# Schematic.net
KiCad netlist of a schematic drawn in Altium Designer
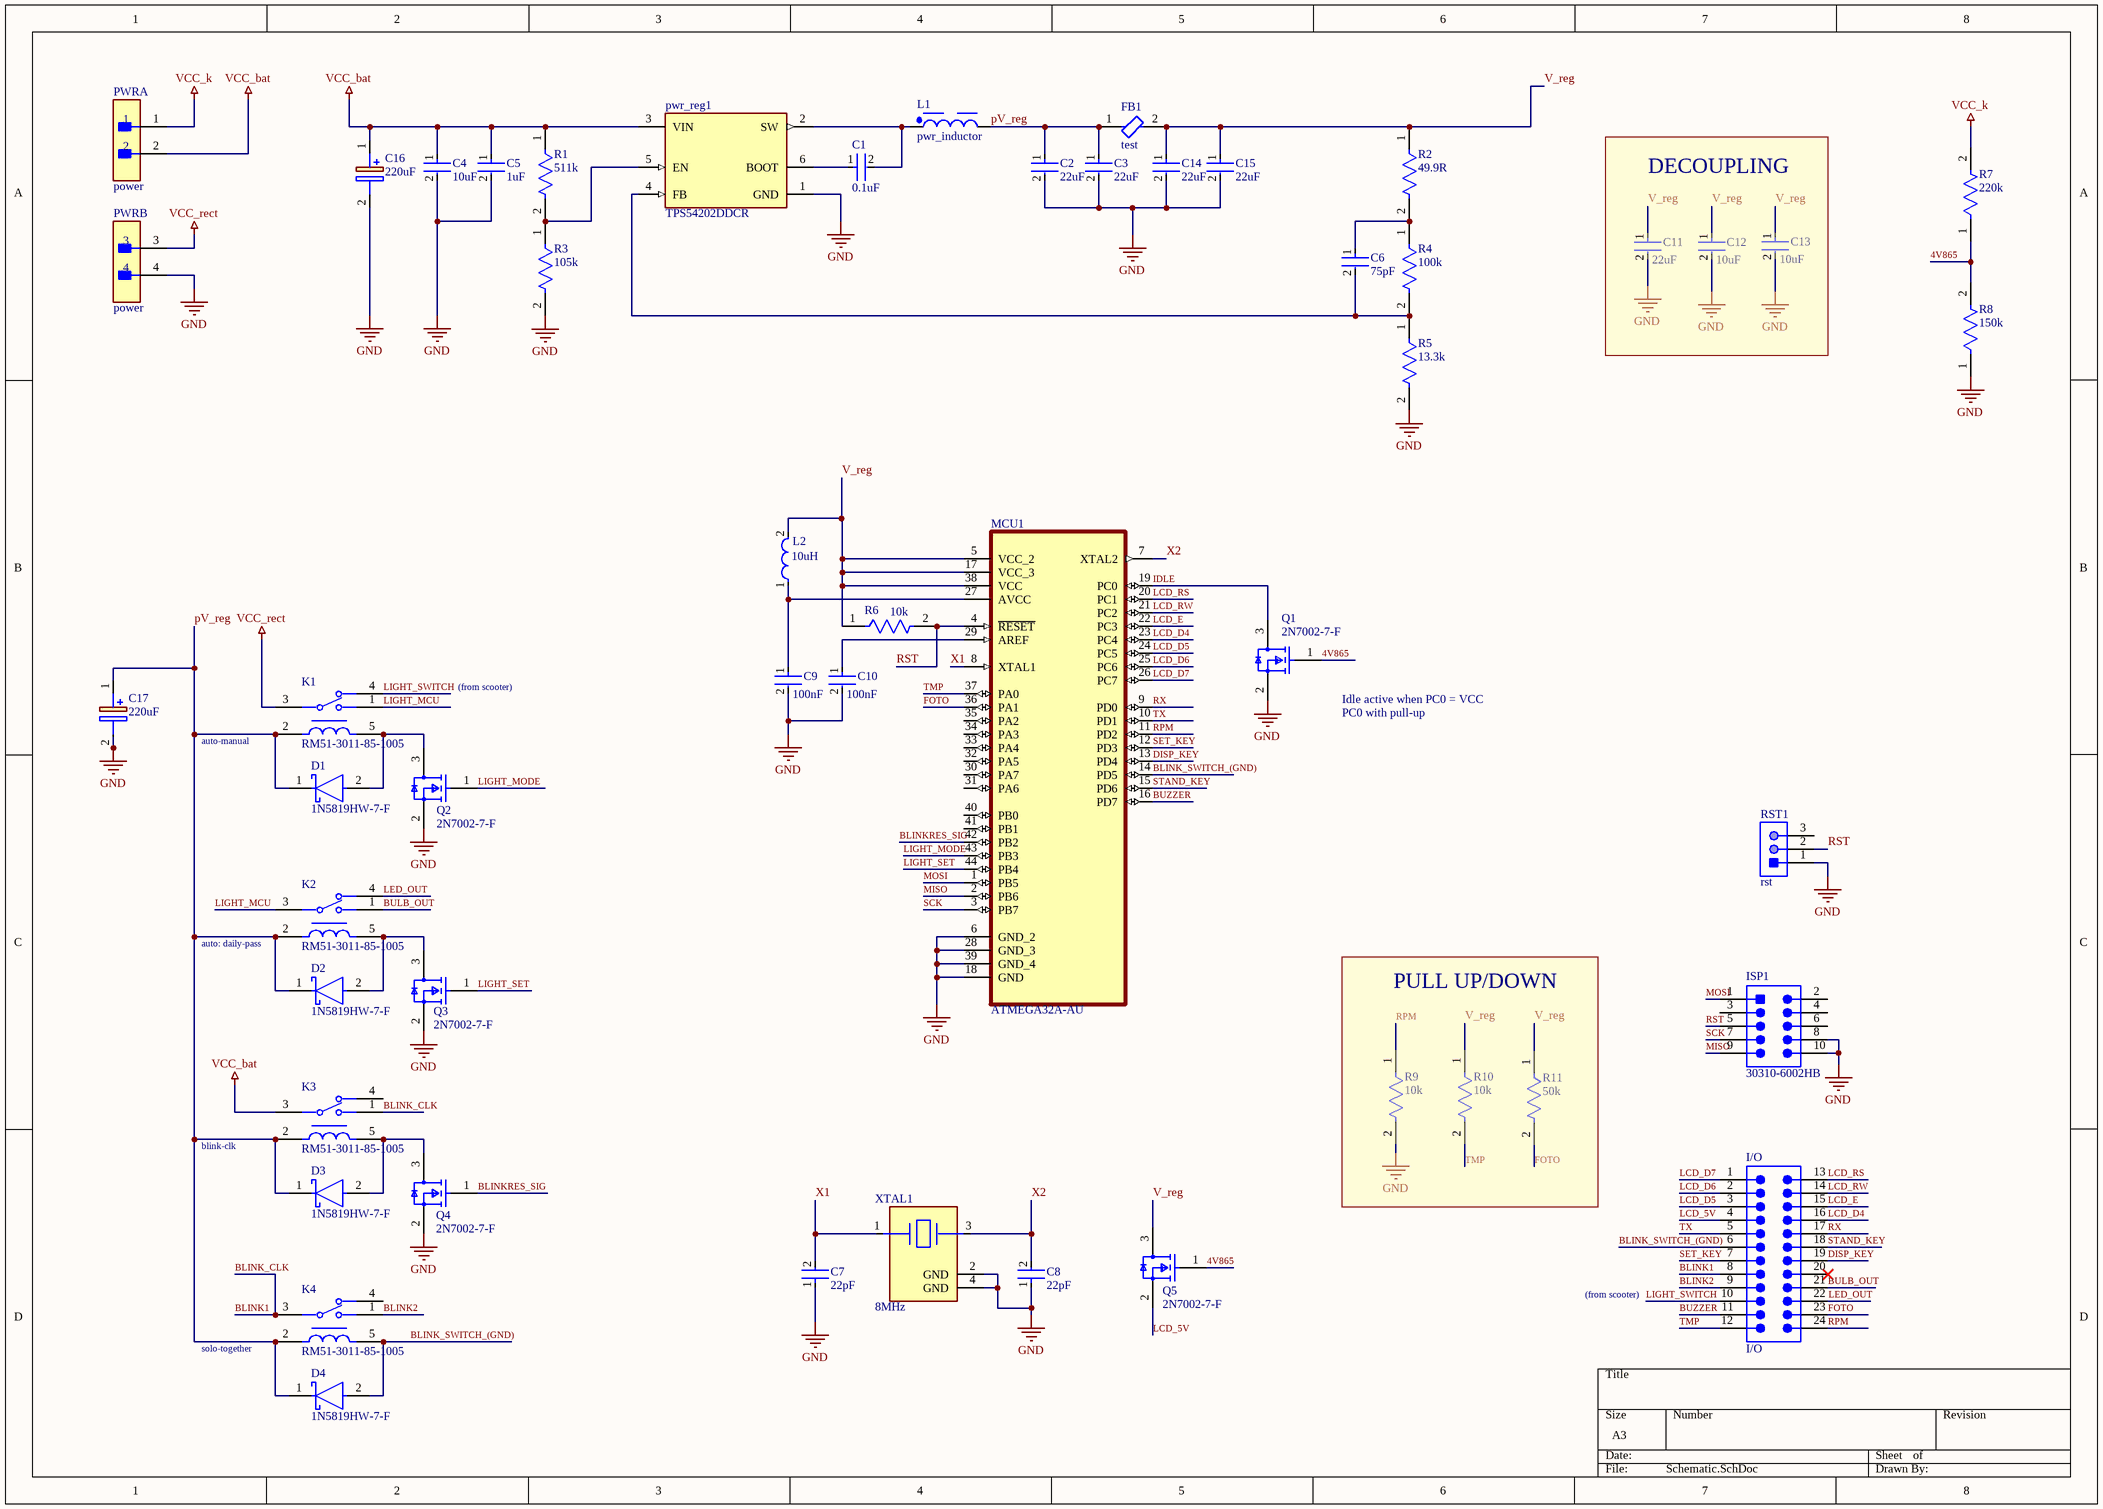
[diagram p0: Schematic.SchDoc]

(export (version "E")
  (design (tool "Eeschema 10.0.6"))
  (components
    (comp (ref "C1")
      (value "0.1uF")
      (footprint "FP-CL10-IPC_A")
      (description "Cap Ceramic 0.1uF 25V SMD 0603")
      (fields (field (name "VOLTAGE") "50V") (field (name "TOLERANCE") "10%"))
      (libsource (lib "Altium Content Vault") (part "b4654b650e69147ec39a6b967a45e02"))
    )
    (comp (ref "C2")
      (value "22uF")
      (footprint "FP-CL10-IPC_A")
      (description "Cap Ceramic 22uF 25V X7R LOW ESR SMD 0603")
      (fields (field (name "VOLTAGE") "50V") (field (name "TOLERANCE") "10%"))
      (libsource (lib "Altium Content Vault") (part "b4654b650e69147ec39a6b967a45e02"))
    )
    (comp (ref "C3")
      (value "22uF")
      (footprint "FP-CL10-IPC_A")
      (description "Cap Ceramic 22uF 25V X7R LOW ESR SMD 0603")
      (fields (field (name "VOLTAGE") "50V") (field (name "TOLERANCE") "10%"))
      (libsource (lib "Altium Content Vault") (part "b4654b650e69147ec39a6b967a45e02"))
    )
    (comp (ref "C4")
      (value "10uF")
      (footprint "FP-CL31-IPC_C")
      (description "CAP CER 10uF 25V X5R 1206")
      (fields (field (name "TOLERANCE") "10%") (field (name "MANUFACTURER") "Samsung"))
      (libsource (lib "Altium Content Vault") (part "11868f565c42a9108669ba33697ecf6"))
    )
    (comp (ref "C5")
      (value "1uF")
      (footprint "FP-CL10-IPC_A")
      (description "Cap Ceramic 1uF 25V SMD 0603")
      (fields (field (name "VOLTAGE") "50V") (field (name "TOLERANCE") "10%"))
      (libsource (lib "Altium Content Vault") (part "b4654b650e69147ec39a6b967a45e02"))
    )
    (comp (ref "C6")
      (value "75pF")
      (footprint "FP-CL10-IPC_A")
      (description "Cap Ceramic 75pF 25V SMD 0603")
      (fields (field (name "VOLTAGE") "50V") (field (name "TOLERANCE") "10%"))
      (libsource (lib "Altium Content Vault") (part "b4654b650e69147ec39a6b967a45e02"))
    )
    (comp (ref "C7")
      (value "22pF")
      (footprint "FP-CL10-IPC_A")
      (description "Cap Ceramic 22pF 25V SMD 0603")
      (fields (field (name "VOLTAGE") "50V") (field (name "TOLERANCE") "10%"))
      (libsource (lib "Altium Content Vault") (part "b4654b650e69147ec39a6b967a45e02"))
    )
    (comp (ref "C8")
      (value "22pF")
      (footprint "FP-CL10-IPC_A")
      (description "Cap Ceramic 22pF 25V SMD 0603")
      (fields (field (name "VOLTAGE") "50V") (field (name "TOLERANCE") "10%"))
      (libsource (lib "Altium Content Vault") (part "b4654b650e69147ec39a6b967a45e02"))
    )
    (comp (ref "C9")
      (value "100nF")
      (footprint "FP-CL10-IPC_A")
      (description "Cap Ceramic 100nF 50V X7R ±10% Pad SMD 0603 +125°C T/R")
      (fields (field (name "VOLTAGE") "50V") (field (name "TOLERANCE") "10%"))
      (libsource (lib "Altium Content Vault") (part "b4654b650e69147ec39a6b967a45e02"))
    )
    (comp (ref "C10")
      (value "100nF")
      (footprint "FP-CL10-IPC_A")
      (description "Cap Ceramic 100nF 50V X7R ±10% Pad SMD 0603 +125°C T/R")
      (fields (field (name "VOLTAGE") "50V") (field (name "TOLERANCE") "10%"))
      (libsource (lib "Altium Content Vault") (part "b4654b650e69147ec39a6b967a45e02"))
    )
    (comp (ref "C11")
      (value "22uF")
      (footprint "FP-CL10-IPC_A")
      (description "Cap Ceramic 22uF 10V X7R ±10% Pad SMD 0603 +125°C T/R")
      (fields (field (name "VOLTAGE") "50V") (field (name "TOLERANCE") "10%"))
      (libsource (lib "Altium Content Vault") (part "b4654b650e69147ec39a6b967a45e02"))
    )
    (comp (ref "C12")
      (value "10uF")
      (footprint "FP-CL10-IPC_A")
      (description "Cap Ceramic 10uF 10V X7R ±10% Pad SMD 0603 +125°C T/R")
      (fields (field (name "VOLTAGE") "50V") (field (name "TOLERANCE") "10%"))
      (libsource (lib "Altium Content Vault") (part "b4654b650e69147ec39a6b967a45e02"))
    )
    (comp (ref "C13")
      (value "10uF")
      (footprint "FP-CL10-IPC_A")
      (description "Cap Ceramic 10uF 10V X7R ±10% Pad SMD 0603 +125°C T/R")
      (fields (field (name "VOLTAGE") "50V") (field (name "TOLERANCE") "10%"))
      (libsource (lib "Altium Content Vault") (part "b4654b650e69147ec39a6b967a45e02"))
    )
    (comp (ref "C14")
      (value "22uF")
      (footprint "FP-CL10-IPC_A")
      (description "Cap Ceramic 22uF 25V X7R LOW ESR SMD 0603")
      (fields (field (name "VOLTAGE") "50V") (field (name "TOLERANCE") "10%"))
      (libsource (lib "Altium Content Vault") (part "b4654b650e69147ec39a6b967a45e02"))
    )
    (comp (ref "C15")
      (value "22uF")
      (footprint "FP-CL10-IPC_A")
      (description "Cap Ceramic 22uF 25V X7R LOW ESR SMD 0603")
      (fields (field (name "VOLTAGE") "50V") (field (name "TOLERANCE") "10%"))
      (libsource (lib "Altium Content Vault") (part "b4654b650e69147ec39a6b967a45e02"))
    )
    (comp (ref "C16")
      (value "220uF")
      (footprint "SamacSys:CAPAE660X810N")
      (description "Cap 16V 220uF\r\n\r\nInput current decap")
      (fields (field (name "MANUFACTURER_PART_NUMBER") "SC1C227M6L07KVR"))
      (libsource (lib "*") (part "SC1C227M6L07KVR"))
    )
    (comp (ref "C17")
      (value "220uF")
      (footprint "SamacSys:CAPAE660X810N")
      (description "Cap 16V 220uF\r\n\r\nRelay coils bulk capacitor")
      (fields (field (name "MANUFACTURER_PART_NUMBER") "SC1C227M6L07KVR"))
      (libsource (lib "*") (part "SC1C227M6L07KVR"))
    )
    (comp (ref "D1")
      (value "1N5819HW-7-F")
      (footprint "FP-SOD123-IPC_A")
      (description "DIODE SCHOTTKY 40V 1A SOD123")
      (libsource (lib "Altium Content Vault") (part "1d6ec82d83fb6aee721767c19dac4b9"))
    )
    (comp (ref "D2")
      (value "1N5819HW-7-F")
      (footprint "FP-SOD123-IPC_A")
      (description "DIODE SCHOTTKY 40V 1A SOD123")
      (libsource (lib "Altium Content Vault") (part "1d6ec82d83fb6aee721767c19dac4b9"))
    )
    (comp (ref "D3")
      (value "1N5819HW-7-F")
      (footprint "FP-SOD123-IPC_A")
      (description "DIODE SCHOTTKY 40V 1A SOD123")
      (libsource (lib "Altium Content Vault") (part "1d6ec82d83fb6aee721767c19dac4b9"))
    )
    (comp (ref "D4")
      (value "1N5819HW-7-F")
      (footprint "FP-SOD123-IPC_A")
      (description "DIODE SCHOTTKY 40V 1A SOD123")
      (libsource (lib "Altium Content Vault") (part "1d6ec82d83fb6aee721767c19dac4b9"))
    )
    (comp (ref "FB1")
      (value "test")
      (footprint "FP-BLM18-0_15-t0_8-IPC_A")
      (description "Chip Ferrite Bead, 0603\r\n\r\nFor testing purpose")
      (fields (field (name "TOLERANCE") "25%"))
      (libsource (lib "Altium Content Vault") (part "5f30dd21d616792df468990f7003faa"))
    )
    (comp (ref "I/O")
      (value "I/O")
      (footprint "649024227222")
      (libsource (lib "Altium Content Vault") (part "Header_Male_2R_24P(A)"))
    )
    (comp (ref "ISP1")
      (value "30310-6002HB")
      (footprint "3M-30310-6002HB-10_V")
      (fields (field (name "MANUFACTURER") "3M"))
      (libsource (lib "Altium Content Vault") (part "CN-2P-M-R10"))
    )
    (comp (ref "K1")
      (value "RM51-3011-85-1005")
      (footprint "FP-1-1721150-0-MFG")
      (description "Relpol\r\nRM51-3011-85-1005\r\nRELAY 10A 5V")
      (fields
        (field (name "MANUFACTURER") "TE")
        (field (name "OCTOPART") "https://octopart.com/1-1721150-0-te+connectivity-41294869")
      )
      (libsource (lib "Altium Content Vault") (part "6d7f6cec76f9d90da65a396cf24d809"))
    )
    (comp (ref "K2")
      (value "RM51-3011-85-1005")
      (footprint "FP-1-1721150-0-MFG")
      (description "Relpol\r\nRM51-3011-85-1005\r\nRELAY 10A 5V")
      (fields
        (field (name "MANUFACTURER") "TE")
        (field (name "OCTOPART") "https://octopart.com/1-1721150-0-te+connectivity-41294869")
      )
      (libsource (lib "Altium Content Vault") (part "6d7f6cec76f9d90da65a396cf24d809"))
    )
    (comp (ref "K3")
      (value "RM51-3011-85-1005")
      (footprint "FP-1-1721150-0-MFG")
      (description "Relpol\r\nRM51-3011-85-1005\r\nRELAY 10A 5V")
      (fields
        (field (name "MANUFACTURER") "TE")
        (field (name "OCTOPART") "https://octopart.com/1-1721150-0-te+connectivity-41294869")
      )
      (libsource (lib "Altium Content Vault") (part "6d7f6cec76f9d90da65a396cf24d809"))
    )
    (comp (ref "K4")
      (value "RM51-3011-85-1005")
      (footprint "FP-1-1721150-0-MFG")
      (description "Relpol\r\nRM51-3011-85-1005\r\nRELAY 10A 5V")
      (fields
        (field (name "MANUFACTURER") "TE")
        (field (name "OCTOPART") "https://octopart.com/1-1721150-0-te+connectivity-41294869")
      )
      (libsource (lib "Altium Content Vault") (part "6d7f6cec76f9d90da65a396cf24d809"))
    )
    (comp (ref "L1")
      (value "pwr_inductor")
      (footprint "WE-PD_7345")
      (description "15uF, 2.7A  HPI0630-150")
      (fields (field (name "TOLERANCE") "20%"))
      (libsource (lib "Altium Content Vault") (part "Inductor - 2"))
    )
    (comp (ref "L2")
      (value "10uH")
      (footprint "FP-CBMF1608-IPC_A")
      (description "SMD Inductors 10uH ±10% 0.38A 0.468Ω 0603")
      (fields (field (name "TOLERANCE") "10%"))
      (libsource (lib "Altium Content Vault") (part "725321dda6339637d4d059423bc1c3c"))
    )
    (comp (ref "MCU1")
      (value "ATMEGA32A-AU")
      (footprint "QFP80P1200X1200X120-44N")
      (description "AVR AVRÂ® ATmega Microcontroller IC 8-Bit 16MHz 32KB (16K x 16) FLASH 44-TQFP (10x10)")
      (fields (field (name "MF") "Microchip"))
      (libsource (lib "ATMEGA32A-AU") (part "ATMEGA32A-AU"))
    )
    (comp (ref "PWR")
      (value "power")
      (footprint "FP-1586042-4-MFG")
      (description "CONN HEADER R/A 4POS 4.2MM")
      (libsource (lib "Altium Content Vault") (part "54be066d535c0aa4221644b3767ed93"))
    )
    (comp (ref "pwr_reg1")
      (value "TPS54202DDCR")
      (footprint "FP-DDC0006A-IPC_B")
      (description "IC REG BUCK ADJ 2A TSOT23-6")
      (libsource (lib "Altium Content Vault") (part "35c2d3f1afc239a386b2ba50eead654"))
    )
    (comp (ref "Q1")
      (value "2N7002-7-F")
      (footprint "FP-SOT23-MFG")
      (description "MOSFET N-CH 60V 115MA SOT23-3")
      (fields (field (name "VOLTAGE") "60V"))
      (libsource (lib "Altium Content Vault") (part "3b9c635fedb024a5347a57b145af9cc"))
    )
    (comp (ref "Q2")
      (value "2N7002-7-F")
      (footprint "FP-SOT23-MFG")
      (description "MOSFET N-CH 60V 115MA SOT23-3")
      (fields (field (name "VOLTAGE") "60V"))
      (libsource (lib "Altium Content Vault") (part "3b9c635fedb024a5347a57b145af9cc"))
    )
    (comp (ref "Q3")
      (value "2N7002-7-F")
      (footprint "FP-SOT23-MFG")
      (description "MOSFET N-CH 60V 115MA SOT23-3")
      (fields (field (name "VOLTAGE") "60V"))
      (libsource (lib "Altium Content Vault") (part "3b9c635fedb024a5347a57b145af9cc"))
    )
    (comp (ref "Q4")
      (value "2N7002-7-F")
      (footprint "FP-SOT23-MFG")
      (description "MOSFET N-CH 60V 115MA SOT23-3")
      (fields (field (name "VOLTAGE") "60V"))
      (libsource (lib "Altium Content Vault") (part "3b9c635fedb024a5347a57b145af9cc"))
    )
    (comp (ref "Q5")
      (value "2N7002-7-F")
      (footprint "FP-SOT23-MFG")
      (description "MOSFET N-CH 60V 115MA SOT23-3")
      (fields (field (name "VOLTAGE") "60V"))
      (libsource (lib "Altium Content Vault") (part "3b9c635fedb024a5347a57b145af9cc"))
    )
    (comp (ref "R1")
      (value "511k")
      (footprint "FP-CRCW0603-e3-IPC_A")
      (description "511kΩ, 0.1W, 0603")
      (fields (field (name "TOLERANCE") "1%"))
      (libsource (lib "Altium Content Vault") (part "1029c3af85768c4190bb7ad29bc67b5"))
    )
    (comp (ref "R2")
      (value "49.9R")
      (footprint "FP-CRCW0603-e3-IPC_A")
      (description "49.9Ω, 0.1W, 0603")
      (fields (field (name "TOLERANCE") "1%"))
      (libsource (lib "Altium Content Vault") (part "1029c3af85768c4190bb7ad29bc67b5"))
    )
    (comp (ref "R3")
      (value "105k")
      (footprint "FP-CRCW0603-e3-IPC_A")
      (description "105kΩ, 0.1W, 0603")
      (fields (field (name "TOLERANCE") "1%"))
      (libsource (lib "Altium Content Vault") (part "1029c3af85768c4190bb7ad29bc67b5"))
    )
    (comp (ref "R4")
      (value "100k")
      (footprint "FP-CRCW0603-e3-IPC_A")
      (description "100kΩ, 0.1W, 0603")
      (fields (field (name "TOLERANCE") "1%"))
      (libsource (lib "Altium Content Vault") (part "1029c3af85768c4190bb7ad29bc67b5"))
    )
    (comp (ref "R5")
      (value "13.3k")
      (footprint "FP-CRCW0603-e3-IPC_A")
      (description "13.3kΩ, 0.1W, 0603")
      (fields (field (name "TOLERANCE") "1%"))
      (libsource (lib "Altium Content Vault") (part "1029c3af85768c4190bb7ad29bc67b5"))
    )
    (comp (ref "R6")
      (value "10k")
      (footprint "FP-CRCW0603-e3-IPC_A")
      (description "10kΩ, 0.1W, 0603")
      (fields (field (name "TOLERANCE") "1%"))
      (libsource (lib "Altium Content Vault") (part "1029c3af85768c4190bb7ad29bc67b5"))
    )
    (comp (ref "R7")
      (value "220k")
      (footprint "FP-CRCW0603-e3-IPC_A")
      (description "220kΩ, 0.1W, 0603")
      (fields (field (name "TOLERANCE") "1%"))
      (libsource (lib "Altium Content Vault") (part "1029c3af85768c4190bb7ad29bc67b5"))
    )
    (comp (ref "R8")
      (value "150k")
      (footprint "FP-CRCW0603-e3-IPC_A")
      (description "150kΩ, 0.1W, 0603")
      (fields (field (name "TOLERANCE") "1%"))
      (libsource (lib "Altium Content Vault") (part "1029c3af85768c4190bb7ad29bc67b5"))
    )
    (comp (ref "R9")
      (value "10k")
      (footprint "FP-CRCW0603-e3-IPC_A")
      (description "10kΩ, 0.1W, 0603")
      (fields (field (name "TOLERANCE") "1%"))
      (libsource (lib "Altium Content Vault") (part "1029c3af85768c4190bb7ad29bc67b5"))
    )
    (comp (ref "R10")
      (value "10k")
      (footprint "FP-CRCW0603-e3-IPC_A")
      (description "10kΩ, 0.1W, 0603")
      (fields (field (name "TOLERANCE") "1%"))
      (libsource (lib "Altium Content Vault") (part "1029c3af85768c4190bb7ad29bc67b5"))
    )
    (comp (ref "R11")
      (value "50k")
      (footprint "FP-CRCW0603-e3-IPC_A")
      (description "50kΩ, 0.1W, 0603")
      (fields (field (name "TOLERANCE") "1%"))
      (libsource (lib "Altium Content Vault") (part "1029c3af85768c4190bb7ad29bc67b5"))
    )
    (comp (ref "RST1")
      (value "rst")
      (footprint "MOLX-22-28-4033_V")
      (description "Male Header, Pitch 2.54 mm, 1 x 3 Position, Height 8.38 mm, Tail Length 3.18 mm, RoHS, Bulk")
      (fields (field (name "MANUFACTURER") "Molex"))
      (libsource (lib "Altium Content Vault") (part "CN-1P-M-R3"))
    )
    (comp (ref "XTAL1")
      (value "8MHz")
      (footprint "FP-LFXTAL055663REEL-MFG")
      (description "LFXTAL055663REEL\r\nCRYSTAL 8.0000MHZ 18PF SMD")
      (libsource (lib "Altium Content Vault") (part "b89083c918a6a788f8f4b4140568890"))
    )
  )
  (nets
    (net (code "1") (name "/4V865") (class "Default")
      (node (ref "Q1") (pin "1") (pinfunction "G_1") (pintype "passive"))
      (node (ref "Q5") (pin "1") (pinfunction "G_1") (pintype "passive"))
      (node (ref "R7") (pin "1") (pinfunction "1_1") (pintype "passive"))
      (node (ref "R8") (pin "2") (pinfunction "2_2") (pintype "passive"))
    )
    (net (code "3") (name "/BLINK1") (class "Default")
      (node (ref "I/O") (pin "8") (pinfunction "8_8") (pintype "passive"))
      (node (ref "K3") (pin "1") (pinfunction "1_1") (pintype "passive"))
      (node (ref "K4") (pin "3") (pinfunction "3_3") (pintype "passive"))
    )
    (net (code "4") (name "/BLINK2") (class "Default")
      (node (ref "I/O") (pin "9") (pinfunction "9_9") (pintype "passive"))
      (node (ref "K4") (pin "1") (pinfunction "1_1") (pintype "passive"))
    )
    (net (code "5") (name "/BLINKRES_SIG") (class "Default")
      (node (ref "MCU1") (pin "42") (pinfunction "PB2_42") (pintype "bidirectional"))
      (node (ref "Q4") (pin "1") (pinfunction "G_1") (pintype "passive"))
    )
    (net (code "6") (name "/BLINK_SWITCH_(GND)") (class "Default")
      (node (ref "D4") (pin "2") (pinfunction "A_2") (pintype "passive"))
      (node (ref "I/O") (pin "6") (pinfunction "6_6") (pintype "passive"))
      (node (ref "K4") (pin "5") (pinfunction "5_5") (pintype "passive"))
      (node (ref "MCU1") (pin "14") (pinfunction "PD5_14") (pintype "bidirectional"))
    )
    (net (code "7") (name "/BULB_OUT") (class "Default")
      (node (ref "I/O") (pin "21") (pinfunction "21_21") (pintype "passive"))
      (node (ref "K2") (pin "1") (pinfunction "1_1") (pintype "passive"))
    )
    (net (code "8") (name "/BUZZER") (class "Default")
      (node (ref "I/O") (pin "11") (pinfunction "11_11") (pintype "passive"))
      (node (ref "MCU1") (pin "16") (pinfunction "PD7_16") (pintype "bidirectional"))
    )
    (net (code "9") (name "/DISP_KEY") (class "Default")
      (node (ref "I/O") (pin "19") (pinfunction "19_19") (pintype "passive"))
      (node (ref "MCU1") (pin "13") (pinfunction "PD4_13") (pintype "bidirectional"))
    )
    (net (code "10") (name "/FOTO") (class "Default")
      (node (ref "I/O") (pin "23") (pinfunction "23_23") (pintype "passive"))
      (node (ref "MCU1") (pin "36") (pinfunction "PA1_36") (pintype "bidirectional"))
      (node (ref "R11") (pin "2") (pinfunction "2_2") (pintype "passive"))
    )
    (net (code "11") (name "/IDLE") (class "Default")
      (node (ref "MCU1") (pin "19") (pinfunction "PC0_19") (pintype "bidirectional"))
      (node (ref "Q1") (pin "3") (pinfunction "D_3") (pintype "passive"))
    )
    (net (code "12") (name "/LCD_5V") (class "Default")
      (node (ref "I/O") (pin "4") (pinfunction "4_4") (pintype "passive"))
      (node (ref "Q5") (pin "2") (pinfunction "S_2") (pintype "passive"))
    )
    (net (code "13") (name "/LCD_D4") (class "Default")
      (node (ref "I/O") (pin "16") (pinfunction "16_16") (pintype "passive"))
      (node (ref "MCU1") (pin "23") (pinfunction "PC4_23") (pintype "bidirectional"))
    )
    (net (code "14") (name "/LCD_D5") (class "Default")
      (node (ref "I/O") (pin "3") (pinfunction "3_3") (pintype "passive"))
      (node (ref "MCU1") (pin "24") (pinfunction "PC5_24") (pintype "bidirectional"))
    )
    (net (code "15") (name "/LCD_D6") (class "Default")
      (node (ref "I/O") (pin "2") (pinfunction "2_2") (pintype "passive"))
      (node (ref "MCU1") (pin "25") (pinfunction "PC6_25") (pintype "bidirectional"))
    )
    (net (code "16") (name "/LCD_D7") (class "Default")
      (node (ref "I/O") (pin "1") (pinfunction "1_1") (pintype "passive"))
      (node (ref "MCU1") (pin "26") (pinfunction "PC7_26") (pintype "bidirectional"))
    )
    (net (code "17") (name "/LCD_E") (class "Default")
      (node (ref "I/O") (pin "15") (pinfunction "15_15") (pintype "passive"))
      (node (ref "MCU1") (pin "22") (pinfunction "PC3_22") (pintype "bidirectional"))
    )
    (net (code "18") (name "/LCD_RS") (class "Default")
      (node (ref "I/O") (pin "13") (pinfunction "13_13") (pintype "passive"))
      (node (ref "MCU1") (pin "20") (pinfunction "PC1_20") (pintype "bidirectional"))
    )
    (net (code "19") (name "/LCD_RW") (class "Default")
      (node (ref "I/O") (pin "14") (pinfunction "14_14") (pintype "passive"))
      (node (ref "MCU1") (pin "21") (pinfunction "PC2_21") (pintype "bidirectional"))
    )
    (net (code "20") (name "/LED_OUT") (class "Default")
      (node (ref "I/O") (pin "22") (pinfunction "22_22") (pintype "passive"))
      (node (ref "K2") (pin "4") (pinfunction "4_4") (pintype "passive"))
    )
    (net (code "21") (name "/LIGHT_MCU") (class "Default")
      (node (ref "K1") (pin "1") (pinfunction "1_1") (pintype "passive"))
      (node (ref "K2") (pin "3") (pinfunction "3_3") (pintype "passive"))
    )
    (net (code "22") (name "/LIGHT_MODE") (class "Default")
      (node (ref "MCU1") (pin "43") (pinfunction "PB3_43") (pintype "bidirectional"))
      (node (ref "Q2") (pin "1") (pinfunction "G_1") (pintype "passive"))
    )
    (net (code "23") (name "/LIGHT_SET") (class "Default")
      (node (ref "MCU1") (pin "44") (pinfunction "PB4_44") (pintype "bidirectional"))
      (node (ref "Q3") (pin "1") (pinfunction "G_1") (pintype "passive"))
    )
    (net (code "24") (name "/LIGHT_SWITCH") (class "Default")
      (node (ref "I/O") (pin "10") (pinfunction "10_10") (pintype "passive"))
      (node (ref "K1") (pin "4") (pinfunction "4_4") (pintype "passive"))
    )
    (net (code "25") (name "/MISO") (class "Default")
      (node (ref "ISP1") (pin "9") (pinfunction "9_9") (pintype "passive"))
      (node (ref "MCU1") (pin "2") (pinfunction "PB6_2") (pintype "bidirectional"))
    )
    (net (code "26") (name "/MOSI") (class "Default")
      (node (ref "ISP1") (pin "1") (pinfunction "1_1") (pintype "passive"))
      (node (ref "MCU1") (pin "1") (pinfunction "PB5_1") (pintype "bidirectional"))
    )
    (net (code "27") (name "/RPM") (class "Default")
      (node (ref "I/O") (pin "24") (pinfunction "24_24") (pintype "passive"))
      (node (ref "MCU1") (pin "11") (pinfunction "PD2_11") (pintype "bidirectional"))
      (node (ref "R9") (pin "1") (pinfunction "1_1") (pintype "passive"))
    )
    (net (code "28") (name "/RST") (class "Default")
      (node (ref "ISP1") (pin "5") (pinfunction "5_5") (pintype "passive"))
      (node (ref "MCU1") (pin "4") (pinfunction "~{RESET}_4") (pintype "input"))
      (node (ref "R6") (pin "2") (pinfunction "2_2") (pintype "passive"))
      (node (ref "RST1") (pin "2") (pinfunction "2_2") (pintype "passive"))
    )
    (net (code "29") (name "/RX") (class "Default")
      (node (ref "I/O") (pin "17") (pinfunction "17_17") (pintype "passive"))
      (node (ref "MCU1") (pin "9") (pinfunction "PD0_9") (pintype "bidirectional"))
    )
    (net (code "30") (name "/SCK") (class "Default")
      (node (ref "ISP1") (pin "7") (pinfunction "7_7") (pintype "passive"))
      (node (ref "MCU1") (pin "3") (pinfunction "PB7_3") (pintype "bidirectional"))
    )
    (net (code "31") (name "/SET_KEY") (class "Default")
      (node (ref "I/O") (pin "7") (pinfunction "7_7") (pintype "passive"))
      (node (ref "MCU1") (pin "12") (pinfunction "PD3_12") (pintype "bidirectional"))
    )
    (net (code "32") (name "/STAND_KEY") (class "Default")
      (node (ref "I/O") (pin "18") (pinfunction "18_18") (pintype "passive"))
      (node (ref "MCU1") (pin "15") (pinfunction "PD6_15") (pintype "bidirectional"))
    )
    (net (code "33") (name "/TMP") (class "Default")
      (node (ref "I/O") (pin "12") (pinfunction "12_12") (pintype "passive"))
      (node (ref "MCU1") (pin "37") (pinfunction "PA0_37") (pintype "bidirectional"))
      (node (ref "R10") (pin "2") (pinfunction "2_2") (pintype "passive"))
    )
    (net (code "34") (name "/TX") (class "Default")
      (node (ref "I/O") (pin "5") (pinfunction "5_5") (pintype "passive"))
      (node (ref "MCU1") (pin "10") (pinfunction "PD1_10") (pintype "bidirectional"))
    )
    (net (code "35") (name "/V_reg") (class "Default")
      (node (ref "C11") (pin "1") (pinfunction "1_1") (pintype "passive"))
      (node (ref "C12") (pin "1") (pinfunction "1_1") (pintype "passive"))
      (node (ref "C13") (pin "1") (pinfunction "1_1") (pintype "passive"))
      (node (ref "C14") (pin "1") (pinfunction "1_1") (pintype "passive"))
      (node (ref "C15") (pin "1") (pinfunction "1_1") (pintype "passive"))
      (node (ref "FB1") (pin "2") (pinfunction "2_2") (pintype "passive"))
      (node (ref "L2") (pin "2") (pinfunction "2_2") (pintype "passive"))
      (node (ref "MCU1") (pin "17") (pinfunction "VCC_3_17") (pintype "power_in"))
      (node (ref "MCU1") (pin "38") (pinfunction "VCC_38") (pintype "power_in"))
      (node (ref "MCU1") (pin "5") (pinfunction "VCC_2_5") (pintype "power_in"))
      (node (ref "Q5") (pin "3") (pinfunction "D_3") (pintype "passive"))
      (node (ref "R10") (pin "1") (pinfunction "1_1") (pintype "passive"))
      (node (ref "R11") (pin "1") (pinfunction "1_1") (pintype "passive"))
      (node (ref "R2") (pin "1") (pinfunction "1_1") (pintype "passive"))
      (node (ref "R6") (pin "1") (pinfunction "1_1") (pintype "passive"))
    )
    (net (code "36") (name "/X1") (class "Default")
      (node (ref "C7") (pin "2") (pinfunction "2_2") (pintype "passive"))
      (node (ref "MCU1") (pin "8") (pinfunction "XTAL1_8") (pintype "input"))
      (node (ref "XTAL1") (pin "1") (pinfunction "1_CRYSTAL_1") (pintype "passive"))
    )
    (net (code "37") (name "/X2") (class "Default")
      (node (ref "C8") (pin "2") (pinfunction "2_2") (pintype "passive"))
      (node (ref "MCU1") (pin "7") (pinfunction "XTAL2_7") (pintype "output"))
      (node (ref "XTAL1") (pin "3") (pinfunction "2_CRYSTAL_3") (pintype "passive"))
    )
    (net (code "38") (name "/pV_reg") (class "Default")
      (node (ref "C17") (pin "1") (pinfunction "+_1") (pintype "passive"))
      (node (ref "C2") (pin "1") (pinfunction "1_1") (pintype "passive"))
      (node (ref "C3") (pin "1") (pinfunction "1_1") (pintype "passive"))
      (node (ref "D1") (pin "1") (pinfunction "C_1") (pintype "passive"))
      (node (ref "D2") (pin "1") (pinfunction "C_1") (pintype "passive"))
      (node (ref "D3") (pin "1") (pinfunction "C_1") (pintype "passive"))
      (node (ref "D4") (pin "1") (pinfunction "C_1") (pintype "passive"))
      (node (ref "FB1") (pin "1") (pinfunction "1_1") (pintype "passive"))
      (node (ref "K1") (pin "2") (pinfunction "2_2") (pintype "passive"))
      (node (ref "K2") (pin "2") (pinfunction "2_2") (pintype "passive"))
      (node (ref "K3") (pin "2") (pinfunction "2_2") (pintype "passive"))
      (node (ref "K4") (pin "2") (pinfunction "2_2") (pintype "passive"))
      (node (ref "L1") (pin "2") (pinfunction "2_2") (pintype "passive"))
    )
    (net (code "39") (name "GND") (class "Default")
      (node (ref "C10") (pin "2") (pinfunction "2_2") (pintype "passive"))
      (node (ref "C11") (pin "2") (pinfunction "2_2") (pintype "passive"))
      (node (ref "C12") (pin "2") (pinfunction "2_2") (pintype "passive"))
      (node (ref "C13") (pin "2") (pinfunction "2_2") (pintype "passive"))
      (node (ref "C14") (pin "2") (pinfunction "2_2") (pintype "passive"))
      (node (ref "C15") (pin "2") (pinfunction "2_2") (pintype "passive"))
      (node (ref "C16") (pin "2") (pinfunction "-_2") (pintype "passive"))
      (node (ref "C17") (pin "2") (pinfunction "-_2") (pintype "passive"))
      (node (ref "C2") (pin "2") (pinfunction "2_2") (pintype "passive"))
      (node (ref "C3") (pin "2") (pinfunction "2_2") (pintype "passive"))
      (node (ref "C4") (pin "2") (pinfunction "2_2") (pintype "passive"))
      (node (ref "C5") (pin "2") (pinfunction "2_2") (pintype "passive"))
      (node (ref "C7") (pin "1") (pinfunction "1_1") (pintype "passive"))
      (node (ref "C8") (pin "1") (pinfunction "1_1") (pintype "passive"))
      (node (ref "C9") (pin "2") (pinfunction "2_2") (pintype "passive"))
      (node (ref "ISP1") (pin "10") (pinfunction "10_10") (pintype "passive"))
      (node (ref "ISP1") (pin "8") (pinfunction "8_8") (pintype "passive"))
      (node (ref "MCU1") (pin "18") (pinfunction "GND_18") (pintype "passive"))
      (node (ref "MCU1") (pin "28") (pinfunction "GND_3_28") (pintype "passive"))
      (node (ref "MCU1") (pin "39") (pinfunction "GND_4_39") (pintype "passive"))
      (node (ref "MCU1") (pin "6") (pinfunction "GND_2_6") (pintype "passive"))
      (node (ref "PWR") (pin "4") (pinfunction "4_4") (pintype "passive"))
      (node (ref "Q1") (pin "2") (pinfunction "S_2") (pintype "passive"))
      (node (ref "Q2") (pin "2") (pinfunction "S_2") (pintype "passive"))
      (node (ref "Q3") (pin "2") (pinfunction "S_2") (pintype "passive"))
      (node (ref "Q4") (pin "2") (pinfunction "S_2") (pintype "passive"))
      (node (ref "R3") (pin "2") (pinfunction "2_2") (pintype "passive"))
      (node (ref "R5") (pin "2") (pinfunction "2_2") (pintype "passive"))
      (node (ref "R8") (pin "1") (pinfunction "1_1") (pintype "passive"))
      (node (ref "R9") (pin "2") (pinfunction "2_2") (pintype "passive"))
      (node (ref "RST1") (pin "1") (pinfunction "1_1") (pintype "passive"))
      (node (ref "XTAL1") (pin "2") (pinfunction "GND_2") (pintype "power_in"))
      (node (ref "XTAL1") (pin "4") (pinfunction "GND_4") (pintype "power_in"))
      (node (ref "pwr_reg1") (pin "1") (pinfunction "GND_1") (pintype "power_in"))
    )
    (net (code "40") (name "Net-(C6-Pad1)") (class "Default")
      (node (ref "C6") (pin "1") (pinfunction "1_1") (pintype "passive"))
      (node (ref "R2") (pin "2") (pinfunction "2_2") (pintype "passive"))
      (node (ref "R4") (pin "1") (pinfunction "1_1") (pintype "passive"))
    )
    (net (code "41") (name "Net-(D1-A)") (class "Default")
      (node (ref "D1") (pin "2") (pinfunction "A_2") (pintype "passive"))
      (node (ref "K1") (pin "5") (pinfunction "5_5") (pintype "passive"))
      (node (ref "Q2") (pin "3") (pinfunction "D_3") (pintype "passive"))
    )
    (net (code "42") (name "Net-(D2-A)") (class "Default")
      (node (ref "D2") (pin "2") (pinfunction "A_2") (pintype "passive"))
      (node (ref "K2") (pin "5") (pinfunction "5_5") (pintype "passive"))
      (node (ref "Q3") (pin "3") (pinfunction "D_3") (pintype "passive"))
    )
    (net (code "43") (name "Net-(D3-A)") (class "Default")
      (node (ref "D3") (pin "2") (pinfunction "A_2") (pintype "passive"))
      (node (ref "K3") (pin "5") (pinfunction "5_5") (pintype "passive"))
      (node (ref "Q4") (pin "3") (pinfunction "D_3") (pintype "passive"))
    )
    (net (code "44") (name "Net-(MCU1-AREF)") (class "Default")
      (node (ref "C10") (pin "1") (pinfunction "1_1") (pintype "passive"))
      (node (ref "MCU1") (pin "29") (pinfunction "AREF_29") (pintype "input"))
    )
    (net (code "45") (name "Net-(MCU1-AVCC)") (class "Default")
      (node (ref "C9") (pin "1") (pinfunction "1_1") (pintype "passive"))
      (node (ref "L2") (pin "1") (pinfunction "1_1") (pintype "passive"))
      (node (ref "MCU1") (pin "27") (pinfunction "AVCC_27") (pintype "power_in"))
    )
    (net (code "46") (name "Net-(pwr_reg1-BOOT)") (class "Default")
      (node (ref "C1") (pin "1") (pinfunction "1_1") (pintype "passive"))
      (node (ref "pwr_reg1") (pin "6") (pinfunction "BOOT_6") (pintype "passive"))
    )
    (net (code "47") (name "Net-(pwr_reg1-EN)") (class "Default")
      (node (ref "R1") (pin "2") (pinfunction "2_2") (pintype "passive"))
      (node (ref "R3") (pin "1") (pinfunction "1_1") (pintype "passive"))
      (node (ref "pwr_reg1") (pin "5") (pinfunction "EN_5") (pintype "input"))
    )
    (net (code "48") (name "Net-(pwr_reg1-FB)") (class "Default")
      (node (ref "C6") (pin "2") (pinfunction "2_2") (pintype "passive"))
      (node (ref "R4") (pin "2") (pinfunction "2_2") (pintype "passive"))
      (node (ref "R5") (pin "1") (pinfunction "1_1") (pintype "passive"))
      (node (ref "pwr_reg1") (pin "4") (pinfunction "FB_4") (pintype "input"))
    )
    (net (code "49") (name "Net-(pwr_reg1-SW)") (class "Default")
      (node (ref "C1") (pin "2") (pinfunction "2_2") (pintype "passive"))
      (node (ref "L1") (pin "1") (pinfunction "1_1") (pintype "passive"))
      (node (ref "pwr_reg1") (pin "2") (pinfunction "SW_2") (pintype "output"))
    )
    (net (code "50") (name "VCC_bat") (class "Default")
      (node (ref "C16") (pin "1") (pinfunction "+_1") (pintype "passive"))
      (node (ref "C4") (pin "1") (pinfunction "1_1") (pintype "passive"))
      (node (ref "C5") (pin "1") (pinfunction "1_1") (pintype "passive"))
      (node (ref "K3") (pin "3") (pinfunction "3_3") (pintype "passive"))
      (node (ref "PWR") (pin "2") (pinfunction "2_2") (pintype "passive"))
      (node (ref "R1") (pin "1") (pinfunction "1_1") (pintype "passive"))
      (node (ref "pwr_reg1") (pin "3") (pinfunction "VIN_3") (pintype "power_in"))
    )
    (net (code "51") (name "VCC_k") (class "Default")
      (node (ref "PWR") (pin "1") (pinfunction "1_1") (pintype "passive"))
      (node (ref "R7") (pin "2") (pinfunction "2_2") (pintype "passive"))
    )
    (net (code "52") (name "VCC_rect") (class "Default")
      (node (ref "K1") (pin "3") (pinfunction "3_3") (pintype "passive"))
      (node (ref "PWR") (pin "3") (pinfunction "3_3") (pintype "passive"))
    )
    (net (code "53") (name "unconnected-(I/O-Pad20)") (class "Default")
      (node (ref "I/O") (pin "20") (pinfunction "20_20") (pintype "passive+no_connect"))
    )
    (net (code "54") (name "unconnected-(ISP1-Pad2)") (class "Default")
      (node (ref "ISP1") (pin "2") (pinfunction "2_2") (pintype "passive"))
    )
    (net (code "55") (name "unconnected-(ISP1-Pad3)") (class "Default")
      (node (ref "ISP1") (pin "3") (pinfunction "3_3") (pintype "passive"))
    )
    (net (code "56") (name "unconnected-(ISP1-Pad4)") (class "Default")
      (node (ref "ISP1") (pin "4") (pinfunction "4_4") (pintype "passive"))
    )
    (net (code "57") (name "unconnected-(ISP1-Pad6)") (class "Default")
      (node (ref "ISP1") (pin "6") (pinfunction "6_6") (pintype "passive"))
    )
    (net (code "58") (name "unconnected-(K3-Pad4)") (class "Default")
      (node (ref "K3") (pin "4") (pinfunction "4_4") (pintype "passive"))
    )
    (net (code "59") (name "unconnected-(K4-Pad4)") (class "Default")
      (node (ref "K4") (pin "4") (pinfunction "4_4") (pintype "passive"))
    )
    (net (code "60") (name "unconnected-(MCU1-PA2-Pad35)") (class "Default")
      (node (ref "MCU1") (pin "35") (pinfunction "PA2_35") (pintype "bidirectional"))
    )
    (net (code "61") (name "unconnected-(MCU1-PA3-Pad34)") (class "Default")
      (node (ref "MCU1") (pin "34") (pinfunction "PA3_34") (pintype "bidirectional"))
    )
    (net (code "62") (name "unconnected-(MCU1-PA4-Pad33)") (class "Default")
      (node (ref "MCU1") (pin "33") (pinfunction "PA4_33") (pintype "bidirectional"))
    )
    (net (code "63") (name "unconnected-(MCU1-PA5-Pad32)") (class "Default")
      (node (ref "MCU1") (pin "32") (pinfunction "PA5_32") (pintype "bidirectional"))
    )
    (net (code "64") (name "unconnected-(MCU1-PA6-Pad31)") (class "Default")
      (node (ref "MCU1") (pin "31") (pinfunction "PA6_31") (pintype "bidirectional"))
    )
    (net (code "65") (name "unconnected-(MCU1-PA7-Pad30)") (class "Default")
      (node (ref "MCU1") (pin "30") (pinfunction "PA7_30") (pintype "bidirectional"))
    )
    (net (code "66") (name "unconnected-(MCU1-PB0-Pad40)") (class "Default")
      (node (ref "MCU1") (pin "40") (pinfunction "PB0_40") (pintype "bidirectional"))
    )
    (net (code "67") (name "unconnected-(MCU1-PB1-Pad41)") (class "Default")
      (node (ref "MCU1") (pin "41") (pinfunction "PB1_41") (pintype "bidirectional"))
    )
    (net (code "68") (name "unconnected-(RST1-Pad3)") (class "Default")
      (node (ref "RST1") (pin "3") (pinfunction "3_3") (pintype "passive"))
    )
  )
)
